# schematic.net
KiCad netlist of a schematic drawn in EasyEDA
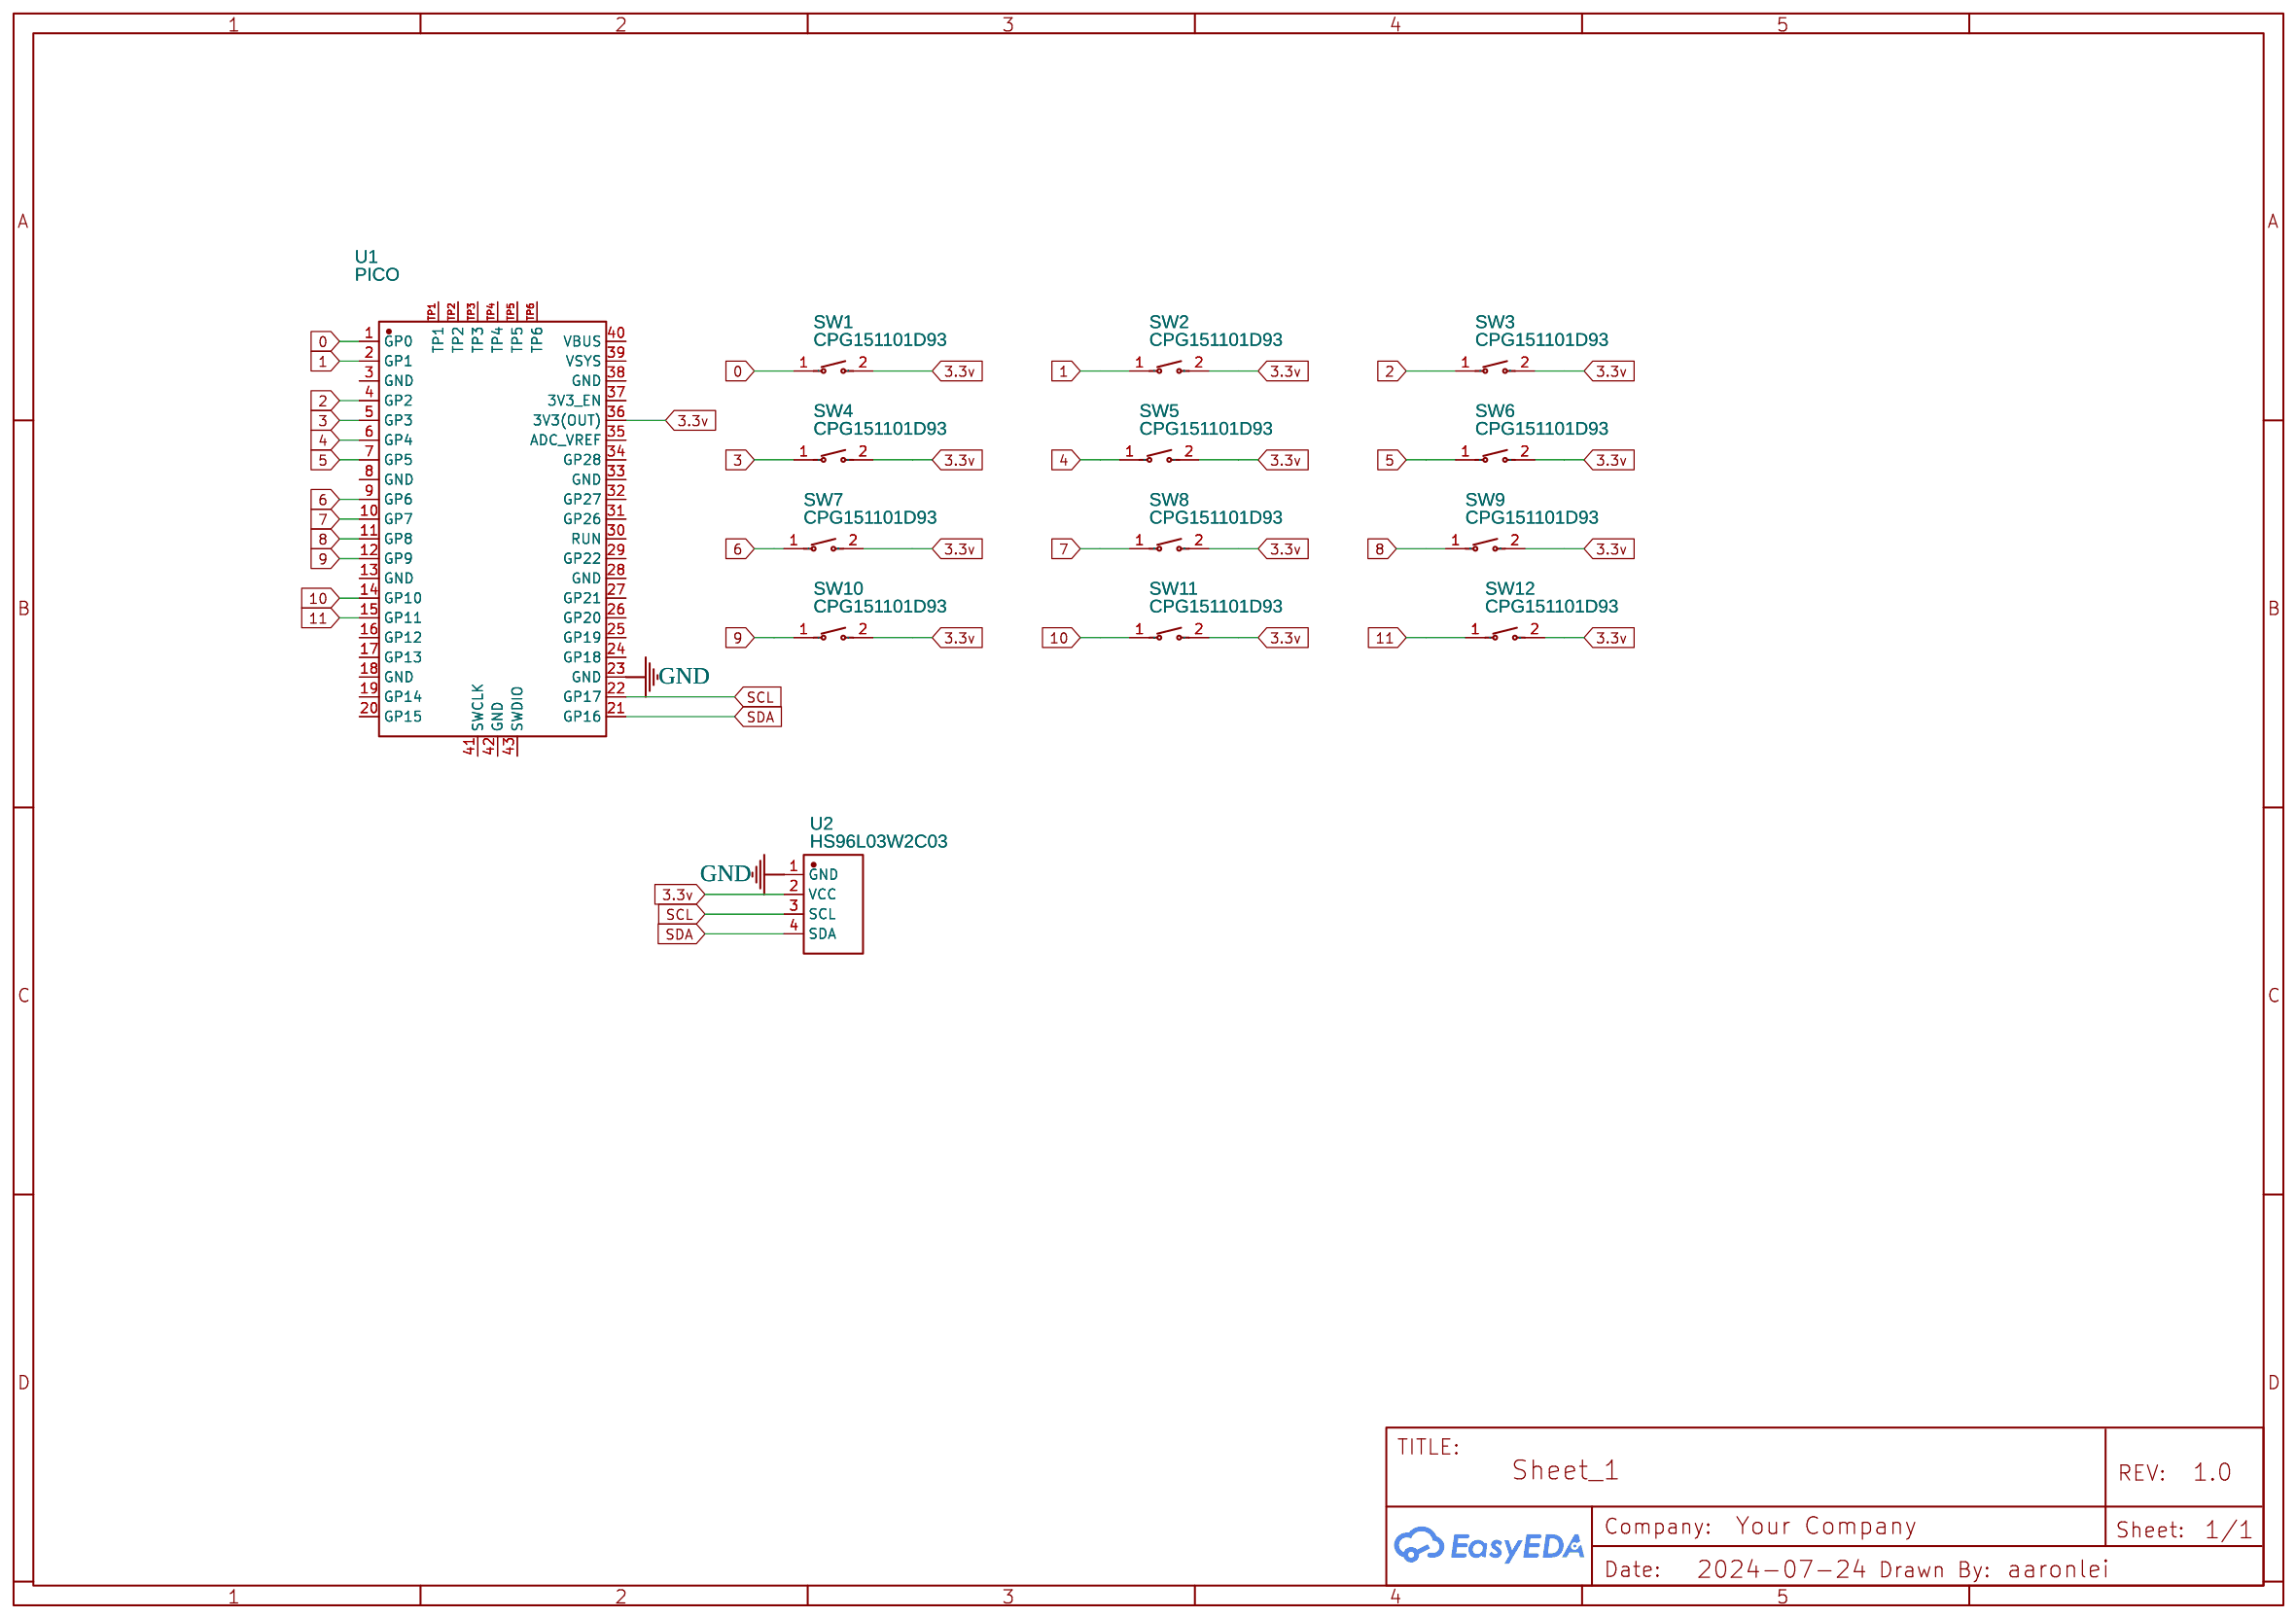
[diagram p0: schematic sheet]

(export (version "E")
  (design (tool "Eeschema 10.0.6"))
  (components
    (comp (ref "SW1")
      (value "CPG151101D93")
      (fields (field (name "Manufacturer") "Kailh(凯华)"))
      (libsource (lib "") (part "CPG151101D93"))
    )
    (comp (ref "SW2")
      (value "CPG151101D93")
      (fields (field (name "Manufacturer") "Kailh(凯华)"))
      (libsource (lib "") (part "CPG151101D93"))
    )
    (comp (ref "SW3")
      (value "CPG151101D93")
      (fields (field (name "Manufacturer") "Kailh(凯华)"))
      (libsource (lib "") (part "CPG151101D93"))
    )
    (comp (ref "SW4")
      (value "CPG151101D93")
      (fields (field (name "Manufacturer") "Kailh(凯华)"))
      (libsource (lib "") (part "CPG151101D93"))
    )
    (comp (ref "SW5")
      (value "CPG151101D93")
      (fields (field (name "Manufacturer") "Kailh(凯华)"))
      (libsource (lib "") (part "CPG151101D93"))
    )
    (comp (ref "SW6")
      (value "CPG151101D93")
      (fields (field (name "Manufacturer") "Kailh(凯华)"))
      (libsource (lib "") (part "CPG151101D93"))
    )
    (comp (ref "SW7")
      (value "CPG151101D93")
      (fields (field (name "Manufacturer") "Kailh(凯华)"))
      (libsource (lib "") (part "CPG151101D93"))
    )
    (comp (ref "SW8")
      (value "CPG151101D93")
      (fields (field (name "Manufacturer") "Kailh(凯华)"))
      (libsource (lib "") (part "CPG151101D93"))
    )
    (comp (ref "SW9")
      (value "CPG151101D93")
      (fields (field (name "Manufacturer") "Kailh(凯华)"))
      (libsource (lib "") (part "CPG151101D93"))
    )
    (comp (ref "SW10")
      (value "CPG151101D93")
      (fields (field (name "Manufacturer") "Kailh(凯华)"))
      (libsource (lib "") (part "CPG151101D93"))
    )
    (comp (ref "SW11")
      (value "CPG151101D93")
      (fields (field (name "Manufacturer") "Kailh(凯华)"))
      (libsource (lib "") (part "CPG151101D93"))
    )
    (comp (ref "SW12")
      (value "CPG151101D93")
      (fields (field (name "Manufacturer") "Kailh(凯华)"))
      (libsource (lib "") (part "CPG151101D93"))
    )
    (comp (ref "U1")
      (value "PICO")
      (fields (field (name "Manufacturer") "Raspberry Pi(树莓派)"))
      (libsource (lib "") (part "PICO"))
    )
    (comp (ref "U2")
      (value "HS96L03W2C03")
      (fields (field (name "Manufacturer") "HS(汉昇)"))
      (libsource (lib "") (part "HS96L03W2C03"))
    )
  )
  (nets
    (net (code "1") (name "0") (class "Default")
      (node (ref "SW1") (pin "1") (pinfunction "1_1") (pintype "unspecified"))
      (node (ref "U1") (pin "1") (pinfunction "GP0_1") (pintype "unspecified"))
    )
    (net (code "2") (name "1") (class "Default")
      (node (ref "SW2") (pin "1") (pinfunction "1_1") (pintype "unspecified"))
      (node (ref "U1") (pin "2") (pinfunction "GP1_2") (pintype "unspecified"))
    )
    (net (code "3") (name "2") (class "Default")
      (node (ref "SW3") (pin "1") (pinfunction "1_1") (pintype "unspecified"))
      (node (ref "U1") (pin "4") (pinfunction "GP2_4") (pintype "unspecified"))
    )
    (net (code "4") (name "3") (class "Default")
      (node (ref "SW4") (pin "1") (pinfunction "1_1") (pintype "unspecified"))
      (node (ref "U1") (pin "5") (pinfunction "GP3_5") (pintype "unspecified"))
    )
    (net (code "5") (name "3.3v") (class "Default")
      (node (ref "SW1") (pin "2") (pinfunction "2_2") (pintype "unspecified"))
      (node (ref "SW10") (pin "2") (pinfunction "2_2") (pintype "unspecified"))
      (node (ref "SW11") (pin "2") (pinfunction "2_2") (pintype "unspecified"))
      (node (ref "SW12") (pin "2") (pinfunction "2_2") (pintype "unspecified"))
      (node (ref "SW2") (pin "2") (pinfunction "2_2") (pintype "unspecified"))
      (node (ref "SW3") (pin "2") (pinfunction "2_2") (pintype "unspecified"))
      (node (ref "SW4") (pin "2") (pinfunction "2_2") (pintype "unspecified"))
      (node (ref "SW5") (pin "2") (pinfunction "2_2") (pintype "unspecified"))
      (node (ref "SW6") (pin "2") (pinfunction "2_2") (pintype "unspecified"))
      (node (ref "SW7") (pin "2") (pinfunction "2_2") (pintype "unspecified"))
      (node (ref "SW8") (pin "2") (pinfunction "2_2") (pintype "unspecified"))
      (node (ref "SW9") (pin "2") (pinfunction "2_2") (pintype "unspecified"))
      (node (ref "U1") (pin "36") (pinfunction "3V3(OUT)_36") (pintype "unspecified"))
      (node (ref "U2") (pin "2") (pinfunction "VCC_2") (pintype "unspecified"))
    )
    (net (code "6") (name "4") (class "Default")
      (node (ref "SW5") (pin "1") (pinfunction "1_1") (pintype "unspecified"))
      (node (ref "U1") (pin "6") (pinfunction "GP4_6") (pintype "unspecified"))
    )
    (net (code "7") (name "5") (class "Default")
      (node (ref "SW6") (pin "1") (pinfunction "1_1") (pintype "unspecified"))
      (node (ref "U1") (pin "7") (pinfunction "GP5_7") (pintype "unspecified"))
    )
    (net (code "8") (name "6") (class "Default")
      (node (ref "SW7") (pin "1") (pinfunction "1_1") (pintype "unspecified"))
      (node (ref "U1") (pin "9") (pinfunction "GP6_9") (pintype "unspecified"))
    )
    (net (code "9") (name "7") (class "Default")
      (node (ref "SW8") (pin "1") (pinfunction "1_1") (pintype "unspecified"))
      (node (ref "U1") (pin "10") (pinfunction "GP7_10") (pintype "unspecified"))
    )
    (net (code "10") (name "8") (class "Default")
      (node (ref "SW9") (pin "1") (pinfunction "1_1") (pintype "unspecified"))
      (node (ref "U1") (pin "11") (pinfunction "GP8_11") (pintype "unspecified"))
    )
    (net (code "11") (name "9") (class "Default")
      (node (ref "SW10") (pin "1") (pinfunction "1_1") (pintype "unspecified"))
      (node (ref "U1") (pin "12") (pinfunction "GP9_12") (pintype "unspecified"))
    )
    (net (code "12") (name "10") (class "Default")
      (node (ref "SW11") (pin "1") (pinfunction "1_1") (pintype "unspecified"))
      (node (ref "U1") (pin "14") (pinfunction "GP10_14") (pintype "unspecified"))
    )
    (net (code "13") (name "11") (class "Default")
      (node (ref "SW12") (pin "1") (pinfunction "1_1") (pintype "unspecified"))
      (node (ref "U1") (pin "15") (pinfunction "GP11_15") (pintype "unspecified"))
    )
    (net (code "14") (name "GND") (class "Default")
      (node (ref "U1") (pin "23") (pinfunction "GND_23") (pintype "unspecified"))
      (node (ref "U2") (pin "1") (pinfunction "GND_1") (pintype "unspecified"))
    )
    (net (code "15") (name "SCL") (class "Default")
      (node (ref "U1") (pin "22") (pinfunction "GP17_22") (pintype "unspecified"))
      (node (ref "U2") (pin "3") (pinfunction "SCL_3") (pintype "unspecified"))
    )
    (net (code "16") (name "SDA") (class "Default")
      (node (ref "U1") (pin "21") (pinfunction "GP16_21") (pintype "unspecified"))
      (node (ref "U2") (pin "4") (pinfunction "SDA_4") (pintype "unspecified"))
    )
    (net (code "17") (name "unconnected-(U1-3V3_EN-Pad37)") (class "Default")
      (node (ref "U1") (pin "37") (pinfunction "3V3_EN_37") (pintype "unspecified"))
    )
    (net (code "18") (name "unconnected-(U1-ADC_VREF-Pad35)") (class "Default")
      (node (ref "U1") (pin "35") (pinfunction "ADC_VREF_35") (pintype "unspecified"))
    )
    (net (code "19") (name "unconnected-(U1-GND-Pad3)") (class "Default")
      (node (ref "U1") (pin "3") (pinfunction "GND_3") (pintype "unspecified"))
    )
    (net (code "20") (name "unconnected-(U1-GND-Pad8)") (class "Default")
      (node (ref "U1") (pin "8") (pinfunction "GND_8") (pintype "unspecified"))
    )
    (net (code "21") (name "unconnected-(U1-GND-Pad13)") (class "Default")
      (node (ref "U1") (pin "13") (pinfunction "GND_13") (pintype "unspecified"))
    )
    (net (code "22") (name "unconnected-(U1-GND-Pad18)") (class "Default")
      (node (ref "U1") (pin "18") (pinfunction "GND_18") (pintype "unspecified"))
    )
    (net (code "23") (name "unconnected-(U1-GND-Pad28)") (class "Default")
      (node (ref "U1") (pin "28") (pinfunction "GND_28") (pintype "unspecified"))
    )
    (net (code "24") (name "unconnected-(U1-GND-Pad33)") (class "Default")
      (node (ref "U1") (pin "33") (pinfunction "GND_33") (pintype "unspecified"))
    )
    (net (code "25") (name "unconnected-(U1-GND-Pad38)") (class "Default")
      (node (ref "U1") (pin "38") (pinfunction "GND_38") (pintype "unspecified"))
    )
    (net (code "26") (name "unconnected-(U1-GND-Pad42)") (class "Default")
      (node (ref "U1") (pin "42") (pinfunction "GND_42") (pintype "unspecified"))
    )
    (net (code "27") (name "unconnected-(U1-GP12-Pad16)") (class "Default")
      (node (ref "U1") (pin "16") (pinfunction "GP12_16") (pintype "unspecified"))
    )
    (net (code "28") (name "unconnected-(U1-GP13-Pad17)") (class "Default")
      (node (ref "U1") (pin "17") (pinfunction "GP13_17") (pintype "unspecified"))
    )
    (net (code "29") (name "unconnected-(U1-GP14-Pad19)") (class "Default")
      (node (ref "U1") (pin "19") (pinfunction "GP14_19") (pintype "unspecified"))
    )
    (net (code "30") (name "unconnected-(U1-GP15-Pad20)") (class "Default")
      (node (ref "U1") (pin "20") (pinfunction "GP15_20") (pintype "unspecified"))
    )
    (net (code "31") (name "unconnected-(U1-GP18-Pad24)") (class "Default")
      (node (ref "U1") (pin "24") (pinfunction "GP18_24") (pintype "unspecified"))
    )
    (net (code "32") (name "unconnected-(U1-GP19-Pad25)") (class "Default")
      (node (ref "U1") (pin "25") (pinfunction "GP19_25") (pintype "unspecified"))
    )
    (net (code "33") (name "unconnected-(U1-GP20-Pad26)") (class "Default")
      (node (ref "U1") (pin "26") (pinfunction "GP20_26") (pintype "unspecified"))
    )
    (net (code "34") (name "unconnected-(U1-GP21-Pad27)") (class "Default")
      (node (ref "U1") (pin "27") (pinfunction "GP21_27") (pintype "unspecified"))
    )
    (net (code "35") (name "unconnected-(U1-GP22-Pad29)") (class "Default")
      (node (ref "U1") (pin "29") (pinfunction "GP22_29") (pintype "unspecified"))
    )
    (net (code "36") (name "unconnected-(U1-GP26-Pad31)") (class "Default")
      (node (ref "U1") (pin "31") (pinfunction "GP26_31") (pintype "unspecified"))
    )
    (net (code "37") (name "unconnected-(U1-GP27-Pad32)") (class "Default")
      (node (ref "U1") (pin "32") (pinfunction "GP27_32") (pintype "unspecified"))
    )
    (net (code "38") (name "unconnected-(U1-GP28-Pad34)") (class "Default")
      (node (ref "U1") (pin "34") (pinfunction "GP28_34") (pintype "unspecified"))
    )
    (net (code "39") (name "unconnected-(U1-PadTP1)") (class "Default")
      (node (ref "U1") (pin "TP1") (pinfunction "TP1_TP1") (pintype "unspecified"))
    )
    (net (code "40") (name "unconnected-(U1-PadTP2)") (class "Default")
      (node (ref "U1") (pin "TP2") (pinfunction "TP2_TP2") (pintype "unspecified"))
    )
    (net (code "41") (name "unconnected-(U1-PadTP3)") (class "Default")
      (node (ref "U1") (pin "TP3") (pinfunction "TP3_TP3") (pintype "unspecified"))
    )
    (net (code "42") (name "unconnected-(U1-PadTP4)") (class "Default")
      (node (ref "U1") (pin "TP4") (pinfunction "TP4_TP4") (pintype "unspecified"))
    )
    (net (code "43") (name "unconnected-(U1-PadTP5)") (class "Default")
      (node (ref "U1") (pin "TP5") (pinfunction "TP5_TP5") (pintype "unspecified"))
    )
    (net (code "44") (name "unconnected-(U1-PadTP6)") (class "Default")
      (node (ref "U1") (pin "TP6") (pinfunction "TP6_TP6") (pintype "unspecified"))
    )
    (net (code "45") (name "unconnected-(U1-RUN-Pad30)") (class "Default")
      (node (ref "U1") (pin "30") (pinfunction "RUN_30") (pintype "unspecified"))
    )
    (net (code "46") (name "unconnected-(U1-SWCLK-Pad41)") (class "Default")
      (node (ref "U1") (pin "41") (pinfunction "SWCLK_41") (pintype "unspecified"))
    )
    (net (code "47") (name "unconnected-(U1-SWDIO-Pad43)") (class "Default")
      (node (ref "U1") (pin "43") (pinfunction "SWDIO_43") (pintype "unspecified"))
    )
    (net (code "48") (name "unconnected-(U1-VBUS-Pad40)") (class "Default")
      (node (ref "U1") (pin "40") (pinfunction "VBUS_40") (pintype "unspecified"))
    )
    (net (code "49") (name "unconnected-(U1-VSYS-Pad39)") (class "Default")
      (node (ref "U1") (pin "39") (pinfunction "VSYS_39") (pintype "unspecified"))
    )
  )
)
